# SCH_Mini-mc-server.net
KiCad netlist of a schematic drawn in EasyEDA
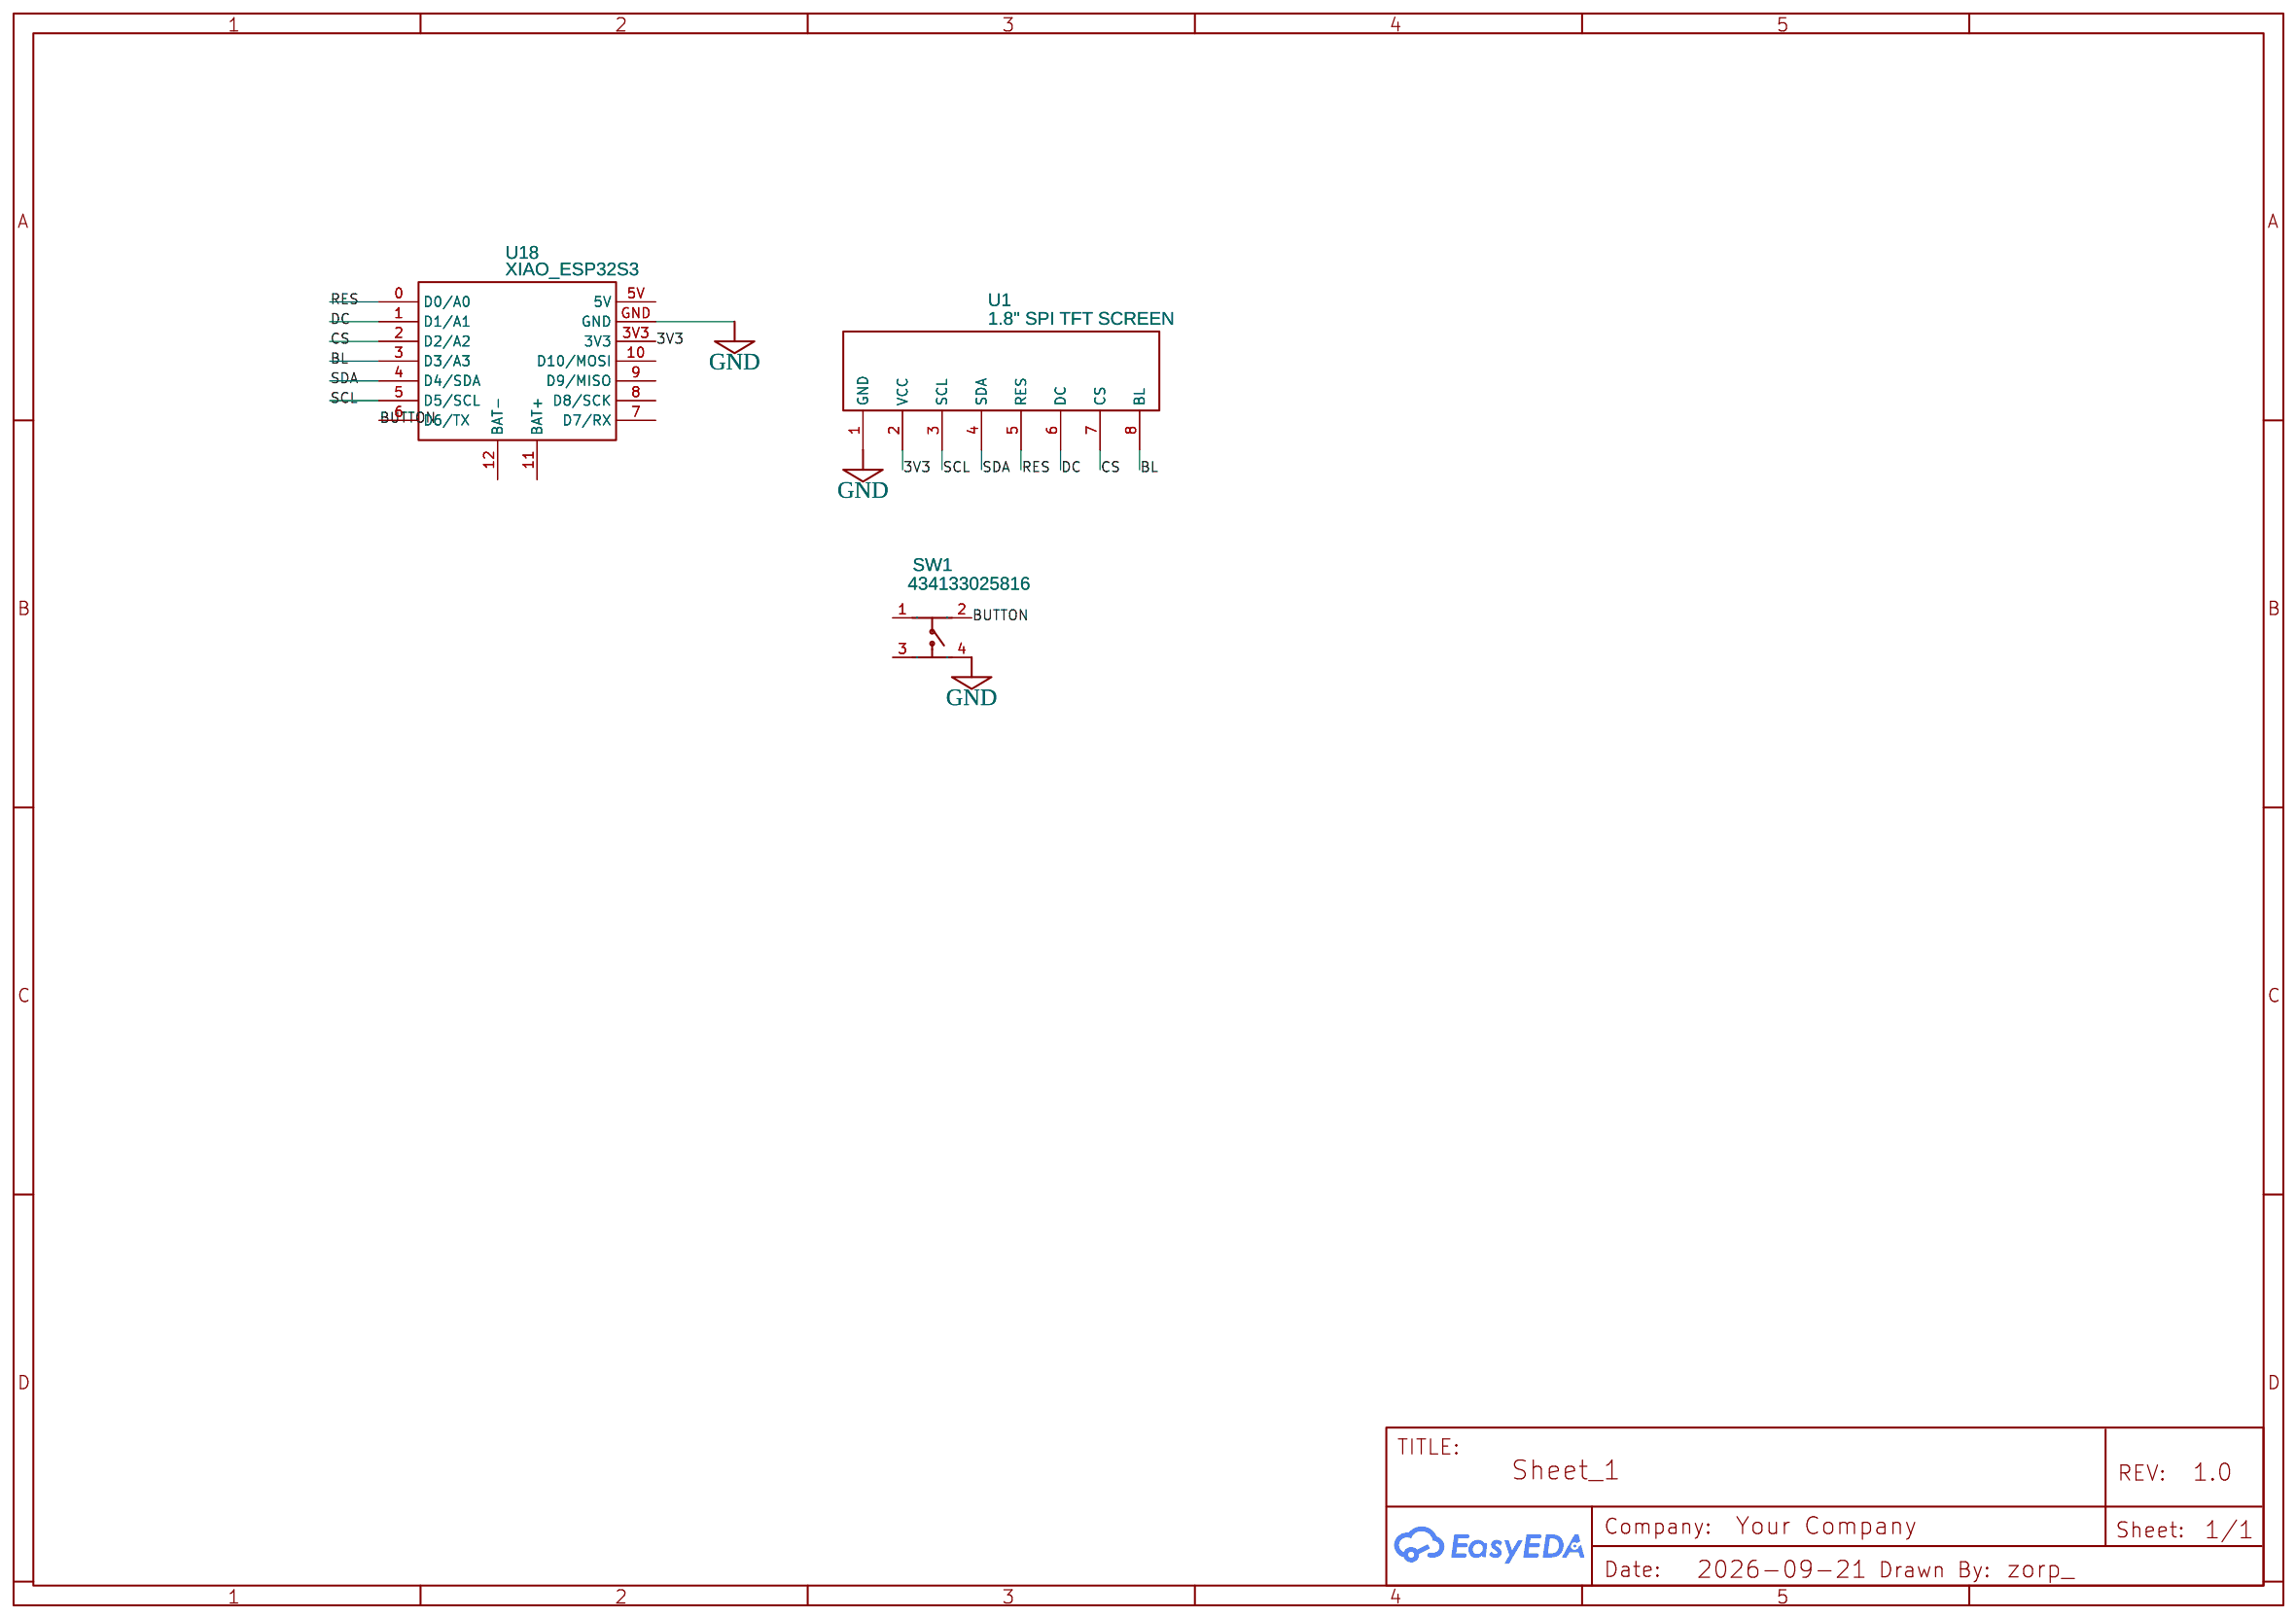
[diagram p0: schematic sheet]

(export (version "E")
  (design (tool "Eeschema 10.0.6"))
  (components
    (comp (ref "SW1")
      (value "434133025816")
      (fields (field (name "Manufacturer") "Wurth(伍尔特)"))
      (libsource (lib "") (part "434133025816"))
    )
    (comp (ref "U1")
      (value "1.8\" SPI TFT SCREEN")
      (libsource (lib "") (part "1.8{dblquote} SPI TFT SCREEN"))
    )
    (comp (ref "U18")
      (value "XIAO_ESP32S3")
      (fields (field (name "Manufacturer Part") "XIAO ESP32S3") (field (name "Manufacturer") "SeeedStudio"))
      (libsource (lib "") (part "XIAO_ESP32S3 COPY"))
    )
  )
  (nets
    (net (code "1") (name "/3V3") (class "Default")
      (node (ref "U1") (pin "2") (pinfunction "VCC_2") (pintype "unspecified"))
      (node (ref "U18") (pin "3V3") (pinfunction "3V3_3V3") (pintype "unspecified"))
    )
    (net (code "2") (name "/BL") (class "Default")
      (node (ref "U1") (pin "8") (pinfunction "BL_8") (pintype "unspecified"))
      (node (ref "U18") (pin "3") (pinfunction "D3/A3_3") (pintype "unspecified"))
    )
    (net (code "3") (name "/BUTTON") (class "Default")
      (node (ref "SW1") (pin "2") (pinfunction "2_2") (pintype "unspecified"))
      (node (ref "U18") (pin "6") (pinfunction "D6/TX_6") (pintype "unspecified"))
    )
    (net (code "4") (name "/CS") (class "Default")
      (node (ref "U1") (pin "7") (pinfunction "CS_7") (pintype "unspecified"))
      (node (ref "U18") (pin "2") (pinfunction "D2/A2_2") (pintype "unspecified"))
    )
    (net (code "5") (name "/DC") (class "Default")
      (node (ref "U1") (pin "6") (pinfunction "DC_6") (pintype "unspecified"))
      (node (ref "U18") (pin "1") (pinfunction "D1/A1_1") (pintype "unspecified"))
    )
    (net (code "6") (name "/RES") (class "Default")
      (node (ref "U1") (pin "5") (pinfunction "RES_5") (pintype "unspecified"))
      (node (ref "U18") (pin "0") (pinfunction "D0/A0_0") (pintype "unspecified"))
    )
    (net (code "7") (name "/SCL") (class "Default")
      (node (ref "U1") (pin "3") (pinfunction "SCL_3") (pintype "unspecified"))
      (node (ref "U18") (pin "5") (pinfunction "D5/SCL_5") (pintype "unspecified"))
    )
    (net (code "8") (name "/SDA") (class "Default")
      (node (ref "U1") (pin "4") (pinfunction "SDA_4") (pintype "unspecified"))
      (node (ref "U18") (pin "4") (pinfunction "D4/SDA_4") (pintype "unspecified"))
    )
    (net (code "9") (name "GND") (class "Default")
      (node (ref "SW1") (pin "4") (pinfunction "4_4") (pintype "unspecified"))
      (node (ref "U1") (pin "1") (pinfunction "GND_1") (pintype "unspecified"))
      (node (ref "U18") (pin "GND") (pinfunction "GND_GND") (pintype "unspecified"))
    )
    (net (code "10") (name "unconnected-(SW1-Pad1)") (class "Default")
      (node (ref "SW1") (pin "1") (pinfunction "1_1") (pintype "unspecified"))
    )
    (net (code "11") (name "unconnected-(SW1-Pad3)") (class "Default")
      (node (ref "SW1") (pin "3") (pinfunction "3_3") (pintype "unspecified"))
    )
    (net (code "12") (name "unconnected-(U18-BAT+-Pad11)") (class "Default")
      (node (ref "U18") (pin "11") (pinfunction "BAT+_11") (pintype "unspecified"))
    )
    (net (code "13") (name "unconnected-(U18-BAT--Pad12)") (class "Default")
      (node (ref "U18") (pin "12") (pinfunction "BAT-_12") (pintype "unspecified"))
    )
    (net (code "14") (name "unconnected-(U18-D7{slash}RX-Pad7)") (class "Default")
      (node (ref "U18") (pin "7") (pinfunction "D7/RX_7") (pintype "unspecified"))
    )
    (net (code "15") (name "unconnected-(U18-D8{slash}SCK-Pad8)") (class "Default")
      (node (ref "U18") (pin "8") (pinfunction "D8/SCK_8") (pintype "unspecified"))
    )
    (net (code "16") (name "unconnected-(U18-D9{slash}MISO-Pad9)") (class "Default")
      (node (ref "U18") (pin "9") (pinfunction "D9/MISO_9") (pintype "unspecified"))
    )
    (net (code "17") (name "unconnected-(U18-D10{slash}MOSI-Pad10)") (class "Default")
      (node (ref "U18") (pin "10") (pinfunction "D10/MOSI_10") (pintype "unspecified"))
    )
    (net (code "18") (name "unconnected-(U18-Pad5V)") (class "Default")
      (node (ref "U18") (pin "5V") (pinfunction "5V_5V") (pintype "unspecified"))
    )
  )
)
